# DIGTITAL.net
KiCad netlist of a schematic drawn in Altium Designer
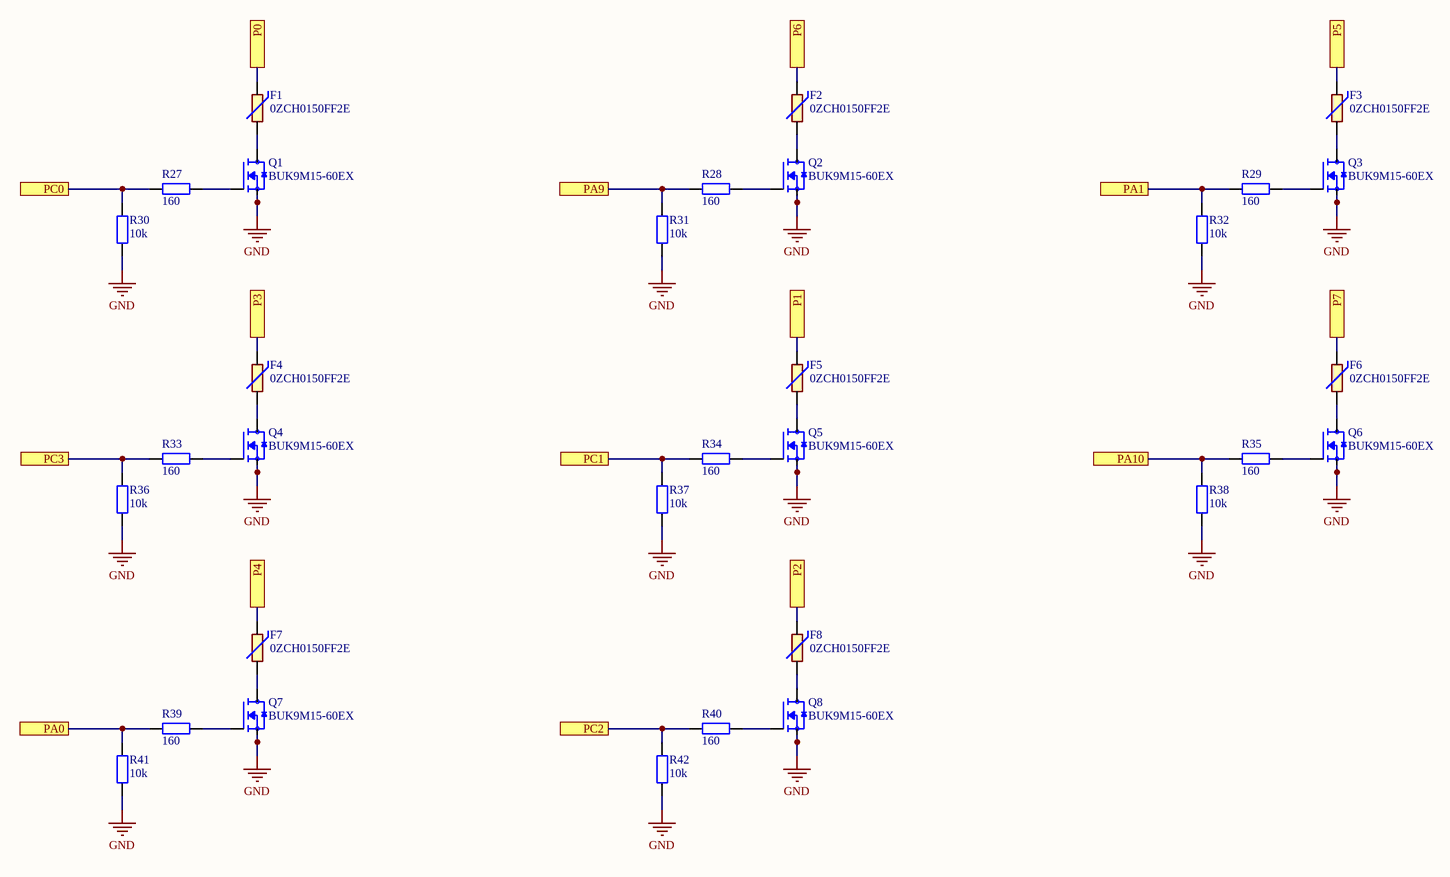
[diagram p0: DIGTITAL.SchDoc]

(export (version "E")
  (design (tool "Eeschema 10.0.6"))
  (components
    (comp (ref "F1")
      (value "0ZCH0150FF2E")
      (footprint "FUSC3225X90N")
      (description "1210 SMT PPTC ¦ 1.50 Ih ¦ 6V")
      (fields (field (name "MF") "Bel Fuse"))
      (libsource (lib "0ZCH0150FF2E") (part "0ZCH0150FF2E"))
    )
    (comp (ref "F2")
      (value "0ZCH0150FF2E")
      (footprint "FUSC3225X90N")
      (description "1210 SMT PPTC ¦ 1.50 Ih ¦ 6V")
      (fields (field (name "MF") "Bel Fuse"))
      (libsource (lib "0ZCH0150FF2E") (part "0ZCH0150FF2E"))
    )
    (comp (ref "F3")
      (value "0ZCH0150FF2E")
      (footprint "FUSC3225X90N")
      (description "1210 SMT PPTC ¦ 1.50 Ih ¦ 6V")
      (fields (field (name "MF") "Bel Fuse"))
      (libsource (lib "0ZCH0150FF2E") (part "0ZCH0150FF2E"))
    )
    (comp (ref "F4")
      (value "0ZCH0150FF2E")
      (footprint "FUSC3225X90N")
      (description "1210 SMT PPTC ¦ 1.50 Ih ¦ 6V")
      (fields (field (name "MF") "Bel Fuse"))
      (libsource (lib "0ZCH0150FF2E") (part "0ZCH0150FF2E"))
    )
    (comp (ref "F5")
      (value "0ZCH0150FF2E")
      (footprint "FUSC3225X90N")
      (description "1210 SMT PPTC ¦ 1.50 Ih ¦ 6V")
      (fields (field (name "MF") "Bel Fuse"))
      (libsource (lib "0ZCH0150FF2E") (part "0ZCH0150FF2E"))
    )
    (comp (ref "F6")
      (value "0ZCH0150FF2E")
      (footprint "FUSC3225X90N")
      (description "1210 SMT PPTC ¦ 1.50 Ih ¦ 6V")
      (fields (field (name "MF") "Bel Fuse"))
      (libsource (lib "0ZCH0150FF2E") (part "0ZCH0150FF2E"))
    )
    (comp (ref "F7")
      (value "0ZCH0150FF2E")
      (footprint "FUSC3225X90N")
      (description "1210 SMT PPTC ¦ 1.50 Ih ¦ 6V")
      (fields (field (name "MF") "Bel Fuse"))
      (libsource (lib "0ZCH0150FF2E") (part "0ZCH0150FF2E"))
    )
    (comp (ref "F8")
      (value "0ZCH0150FF2E")
      (footprint "FUSC3225X90N")
      (description "1210 SMT PPTC ¦ 1.50 Ih ¦ 6V")
      (fields (field (name "MF") "Bel Fuse"))
      (libsource (lib "0ZCH0150FF2E") (part "0ZCH0150FF2E"))
    )
    (comp (ref "Q1")
      (value "BUK9M15-60EX")
      (footprint "TRANS_BUK9M15-60EX")
      (description "Bá»™ chuyá»ƒn Ä‘á»•i N-Channel 60 V 47A (Tc) 75W (Tc) gáº¯n bá» máº·t LFPAK33")
      (fields (field (name "MF") "Nexperia USA"))
      (libsource (lib "BUK9M15-60EX") (part "BUK9M15-60EX"))
    )
    (comp (ref "Q2")
      (value "BUK9M15-60EX")
      (footprint "TRANS_BUK9M15-60EX")
      (description "Bá»™ chuyá»ƒn Ä‘á»•i N-Channel 60 V 47A (Tc) 75W (Tc) gáº¯n bá» máº·t LFPAK33")
      (fields (field (name "MF") "Nexperia USA"))
      (libsource (lib "BUK9M15-60EX") (part "BUK9M15-60EX"))
    )
    (comp (ref "Q3")
      (value "BUK9M15-60EX")
      (footprint "TRANS_BUK9M15-60EX")
      (description "Bá»™ chuyá»ƒn Ä‘á»•i N-Channel 60 V 47A (Tc) 75W (Tc) gáº¯n bá» máº·t LFPAK33")
      (fields (field (name "MF") "Nexperia USA"))
      (libsource (lib "BUK9M15-60EX") (part "BUK9M15-60EX"))
    )
    (comp (ref "Q4")
      (value "BUK9M15-60EX")
      (footprint "TRANS_BUK9M15-60EX")
      (description "Bá»™ chuyá»ƒn Ä‘á»•i N-Channel 60 V 47A (Tc) 75W (Tc) gáº¯n bá» máº·t LFPAK33")
      (fields (field (name "MF") "Nexperia USA"))
      (libsource (lib "BUK9M15-60EX") (part "BUK9M15-60EX"))
    )
    (comp (ref "Q5")
      (value "BUK9M15-60EX")
      (footprint "TRANS_BUK9M15-60EX")
      (description "Bá»™ chuyá»ƒn Ä‘á»•i N-Channel 60 V 47A (Tc) 75W (Tc) gáº¯n bá» máº·t LFPAK33")
      (fields (field (name "MF") "Nexperia USA"))
      (libsource (lib "BUK9M15-60EX") (part "BUK9M15-60EX"))
    )
    (comp (ref "Q6")
      (value "BUK9M15-60EX")
      (footprint "TRANS_BUK9M15-60EX")
      (description "Bá»™ chuyá»ƒn Ä‘á»•i N-Channel 60 V 47A (Tc) 75W (Tc) gáº¯n bá» máº·t LFPAK33")
      (fields (field (name "MF") "Nexperia USA"))
      (libsource (lib "BUK9M15-60EX") (part "BUK9M15-60EX"))
    )
    (comp (ref "Q7")
      (value "BUK9M15-60EX")
      (footprint "TRANS_BUK9M15-60EX")
      (description "Bá»™ chuyá»ƒn Ä‘á»•i N-Channel 60 V 47A (Tc) 75W (Tc) gáº¯n bá» máº·t LFPAK33")
      (fields (field (name "MF") "Nexperia USA"))
      (libsource (lib "BUK9M15-60EX") (part "BUK9M15-60EX"))
    )
    (comp (ref "Q8")
      (value "BUK9M15-60EX")
      (footprint "TRANS_BUK9M15-60EX")
      (description "Bá»™ chuyá»ƒn Ä‘á»•i N-Channel 60 V 47A (Tc) 75W (Tc) gáº¯n bá» máº·t LFPAK33")
      (fields (field (name "MF") "Nexperia USA"))
      (libsource (lib "BUK9M15-60EX") (part "BUK9M15-60EX"))
    )
    (comp (ref "R27")
      (value "160")
      (footprint "tro smd 0603")
      (description "RES")
      (libsource (lib "AUSB") (part "Tro 0603 1% 10k"))
    )
    (comp (ref "R28")
      (value "160")
      (footprint "tro smd 0603")
      (description "RES")
      (libsource (lib "AUSB") (part "Tro 0603 1% 10k"))
    )
    (comp (ref "R29")
      (value "160")
      (footprint "tro smd 0603")
      (description "RES")
      (libsource (lib "AUSB") (part "Tro 0603 1% 10k"))
    )
    (comp (ref "R30")
      (value "10k")
      (footprint "tro smd 0603")
      (description "RES")
      (libsource (lib "AUSB") (part "Tro 0603 1% 10k"))
    )
    (comp (ref "R31")
      (value "10k")
      (footprint "tro smd 0603")
      (description "RES")
      (libsource (lib "AUSB") (part "Tro 0603 1% 10k"))
    )
    (comp (ref "R32")
      (value "10k")
      (footprint "tro smd 0603")
      (description "RES")
      (libsource (lib "AUSB") (part "Tro 0603 1% 10k"))
    )
    (comp (ref "R33")
      (value "160")
      (footprint "tro smd 0603")
      (description "RES")
      (libsource (lib "AUSB") (part "Tro 0603 1% 10k"))
    )
    (comp (ref "R34")
      (value "160")
      (footprint "tro smd 0603")
      (description "RES")
      (libsource (lib "AUSB") (part "Tro 0603 1% 10k"))
    )
    (comp (ref "R35")
      (value "160")
      (footprint "tro smd 0603")
      (description "RES")
      (libsource (lib "AUSB") (part "Tro 0603 1% 10k"))
    )
    (comp (ref "R36")
      (value "10k")
      (footprint "tro smd 0603")
      (description "RES")
      (libsource (lib "AUSB") (part "Tro 0603 1% 10k"))
    )
    (comp (ref "R37")
      (value "10k")
      (footprint "tro smd 0603")
      (description "RES")
      (libsource (lib "AUSB") (part "Tro 0603 1% 10k"))
    )
    (comp (ref "R38")
      (value "10k")
      (footprint "tro smd 0603")
      (description "RES")
      (libsource (lib "AUSB") (part "Tro 0603 1% 10k"))
    )
    (comp (ref "R39")
      (value "160")
      (footprint "tro smd 0603")
      (description "RES")
      (libsource (lib "AUSB") (part "Tro 0603 1% 10k"))
    )
    (comp (ref "R40")
      (value "160")
      (footprint "tro smd 0603")
      (description "RES")
      (libsource (lib "AUSB") (part "Tro 0603 1% 10k"))
    )
    (comp (ref "R41")
      (value "10k")
      (footprint "tro smd 0603")
      (description "RES")
      (libsource (lib "AUSB") (part "Tro 0603 1% 10k"))
    )
    (comp (ref "R42")
      (value "10k")
      (footprint "tro smd 0603")
      (description "RES")
      (libsource (lib "AUSB") (part "Tro 0603 1% 10k"))
    )
  )
  (nets
    (net (code "1") (name "/P0") (class "Default")
      (node (ref "F1") (pin "1") (pinfunction "1_1") (pintype "passive"))
    )
    (net (code "2") (name "/P1") (class "Default")
      (node (ref "F5") (pin "1") (pinfunction "1_1") (pintype "passive"))
    )
    (net (code "3") (name "/P2") (class "Default")
      (node (ref "F8") (pin "1") (pinfunction "1_1") (pintype "passive"))
    )
    (net (code "4") (name "/P3") (class "Default")
      (node (ref "F4") (pin "1") (pinfunction "1_1") (pintype "passive"))
    )
    (net (code "5") (name "/P4") (class "Default")
      (node (ref "F7") (pin "1") (pinfunction "1_1") (pintype "passive"))
    )
    (net (code "6") (name "/P5") (class "Default")
      (node (ref "F3") (pin "1") (pinfunction "1_1") (pintype "passive"))
    )
    (net (code "7") (name "/P6") (class "Default")
      (node (ref "F2") (pin "1") (pinfunction "1_1") (pintype "passive"))
    )
    (net (code "8") (name "/P7") (class "Default")
      (node (ref "F6") (pin "1") (pinfunction "1_1") (pintype "passive"))
    )
    (net (code "9") (name "/PA0") (class "Default")
      (node (ref "R39") (pin "1") (pinfunction "1_1") (pintype "passive"))
      (node (ref "R41") (pin "2") (pinfunction "2_2") (pintype "passive"))
    )
    (net (code "10") (name "/PA1") (class "Default")
      (node (ref "R29") (pin "1") (pinfunction "1_1") (pintype "passive"))
      (node (ref "R32") (pin "2") (pinfunction "2_2") (pintype "passive"))
    )
    (net (code "11") (name "/PA9") (class "Default")
      (node (ref "R28") (pin "1") (pinfunction "1_1") (pintype "passive"))
      (node (ref "R31") (pin "2") (pinfunction "2_2") (pintype "passive"))
    )
    (net (code "12") (name "/PA10") (class "Default")
      (node (ref "R35") (pin "1") (pinfunction "1_1") (pintype "passive"))
      (node (ref "R38") (pin "2") (pinfunction "2_2") (pintype "passive"))
    )
    (net (code "13") (name "/PC0") (class "Default")
      (node (ref "R27") (pin "1") (pinfunction "1_1") (pintype "passive"))
      (node (ref "R30") (pin "2") (pinfunction "2_2") (pintype "passive"))
    )
    (net (code "14") (name "/PC1") (class "Default")
      (node (ref "R34") (pin "1") (pinfunction "1_1") (pintype "passive"))
      (node (ref "R37") (pin "2") (pinfunction "2_2") (pintype "passive"))
    )
    (net (code "15") (name "/PC2") (class "Default")
      (node (ref "R40") (pin "1") (pinfunction "1_1") (pintype "passive"))
      (node (ref "R42") (pin "2") (pinfunction "2_2") (pintype "passive"))
    )
    (net (code "16") (name "/PC3") (class "Default")
      (node (ref "R33") (pin "1") (pinfunction "1_1") (pintype "passive"))
      (node (ref "R36") (pin "2") (pinfunction "2_2") (pintype "passive"))
    )
    (net (code "17") (name "GND") (class "Default")
      (node (ref "Q1") (pin "1") (pinfunction "S_1") (pintype "passive"))
      (node (ref "Q1") (pin "2") (pinfunction "S_2") (pintype "passive"))
      (node (ref "Q1") (pin "3") (pinfunction "S_3") (pintype "passive"))
      (node (ref "Q2") (pin "1") (pinfunction "S_1") (pintype "passive"))
      (node (ref "Q2") (pin "2") (pinfunction "S_2") (pintype "passive"))
      (node (ref "Q2") (pin "3") (pinfunction "S_3") (pintype "passive"))
      (node (ref "Q3") (pin "1") (pinfunction "S_1") (pintype "passive"))
      (node (ref "Q3") (pin "2") (pinfunction "S_2") (pintype "passive"))
      (node (ref "Q3") (pin "3") (pinfunction "S_3") (pintype "passive"))
      (node (ref "Q4") (pin "1") (pinfunction "S_1") (pintype "passive"))
      (node (ref "Q4") (pin "2") (pinfunction "S_2") (pintype "passive"))
      (node (ref "Q4") (pin "3") (pinfunction "S_3") (pintype "passive"))
      (node (ref "Q5") (pin "1") (pinfunction "S_1") (pintype "passive"))
      (node (ref "Q5") (pin "2") (pinfunction "S_2") (pintype "passive"))
      (node (ref "Q5") (pin "3") (pinfunction "S_3") (pintype "passive"))
      (node (ref "Q6") (pin "1") (pinfunction "S_1") (pintype "passive"))
      (node (ref "Q6") (pin "2") (pinfunction "S_2") (pintype "passive"))
      (node (ref "Q6") (pin "3") (pinfunction "S_3") (pintype "passive"))
      (node (ref "Q7") (pin "1") (pinfunction "S_1") (pintype "passive"))
      (node (ref "Q7") (pin "2") (pinfunction "S_2") (pintype "passive"))
      (node (ref "Q7") (pin "3") (pinfunction "S_3") (pintype "passive"))
      (node (ref "Q8") (pin "1") (pinfunction "S_1") (pintype "passive"))
      (node (ref "Q8") (pin "2") (pinfunction "S_2") (pintype "passive"))
      (node (ref "Q8") (pin "3") (pinfunction "S_3") (pintype "passive"))
      (node (ref "R30") (pin "1") (pinfunction "1_1") (pintype "passive"))
      (node (ref "R31") (pin "1") (pinfunction "1_1") (pintype "passive"))
      (node (ref "R32") (pin "1") (pinfunction "1_1") (pintype "passive"))
      (node (ref "R36") (pin "1") (pinfunction "1_1") (pintype "passive"))
      (node (ref "R37") (pin "1") (pinfunction "1_1") (pintype "passive"))
      (node (ref "R38") (pin "1") (pinfunction "1_1") (pintype "passive"))
      (node (ref "R41") (pin "1") (pinfunction "1_1") (pintype "passive"))
      (node (ref "R42") (pin "1") (pinfunction "1_1") (pintype "passive"))
    )
    (net (code "18") (name "Net-(Q1-D)") (class "Default")
      (node (ref "F1") (pin "2") (pinfunction "2_2") (pintype "passive"))
      (node (ref "Q1") (pin "5") (pinfunction "D_5") (pintype "passive"))
    )
    (net (code "19") (name "Net-(Q1-G)") (class "Default")
      (node (ref "Q1") (pin "4") (pinfunction "G_4") (pintype "passive"))
      (node (ref "R27") (pin "2") (pinfunction "2_2") (pintype "passive"))
    )
    (net (code "20") (name "Net-(Q2-D)") (class "Default")
      (node (ref "F2") (pin "2") (pinfunction "2_2") (pintype "passive"))
      (node (ref "Q2") (pin "5") (pinfunction "D_5") (pintype "passive"))
    )
    (net (code "21") (name "Net-(Q2-G)") (class "Default")
      (node (ref "Q2") (pin "4") (pinfunction "G_4") (pintype "passive"))
      (node (ref "R28") (pin "2") (pinfunction "2_2") (pintype "passive"))
    )
    (net (code "22") (name "Net-(Q3-D)") (class "Default")
      (node (ref "F3") (pin "2") (pinfunction "2_2") (pintype "passive"))
      (node (ref "Q3") (pin "5") (pinfunction "D_5") (pintype "passive"))
    )
    (net (code "23") (name "Net-(Q3-G)") (class "Default")
      (node (ref "Q3") (pin "4") (pinfunction "G_4") (pintype "passive"))
      (node (ref "R29") (pin "2") (pinfunction "2_2") (pintype "passive"))
    )
    (net (code "24") (name "Net-(Q4-D)") (class "Default")
      (node (ref "F4") (pin "2") (pinfunction "2_2") (pintype "passive"))
      (node (ref "Q4") (pin "5") (pinfunction "D_5") (pintype "passive"))
    )
    (net (code "25") (name "Net-(Q4-G)") (class "Default")
      (node (ref "Q4") (pin "4") (pinfunction "G_4") (pintype "passive"))
      (node (ref "R33") (pin "2") (pinfunction "2_2") (pintype "passive"))
    )
    (net (code "26") (name "Net-(Q5-D)") (class "Default")
      (node (ref "F5") (pin "2") (pinfunction "2_2") (pintype "passive"))
      (node (ref "Q5") (pin "5") (pinfunction "D_5") (pintype "passive"))
    )
    (net (code "27") (name "Net-(Q5-G)") (class "Default")
      (node (ref "Q5") (pin "4") (pinfunction "G_4") (pintype "passive"))
      (node (ref "R34") (pin "2") (pinfunction "2_2") (pintype "passive"))
    )
    (net (code "28") (name "Net-(Q6-D)") (class "Default")
      (node (ref "F6") (pin "2") (pinfunction "2_2") (pintype "passive"))
      (node (ref "Q6") (pin "5") (pinfunction "D_5") (pintype "passive"))
    )
    (net (code "29") (name "Net-(Q6-G)") (class "Default")
      (node (ref "Q6") (pin "4") (pinfunction "G_4") (pintype "passive"))
      (node (ref "R35") (pin "2") (pinfunction "2_2") (pintype "passive"))
    )
    (net (code "30") (name "Net-(Q7-D)") (class "Default")
      (node (ref "F7") (pin "2") (pinfunction "2_2") (pintype "passive"))
      (node (ref "Q7") (pin "5") (pinfunction "D_5") (pintype "passive"))
    )
    (net (code "31") (name "Net-(Q7-G)") (class "Default")
      (node (ref "Q7") (pin "4") (pinfunction "G_4") (pintype "passive"))
      (node (ref "R39") (pin "2") (pinfunction "2_2") (pintype "passive"))
    )
    (net (code "32") (name "Net-(Q8-D)") (class "Default")
      (node (ref "F8") (pin "2") (pinfunction "2_2") (pintype "passive"))
      (node (ref "Q8") (pin "5") (pinfunction "D_5") (pintype "passive"))
    )
    (net (code "33") (name "Net-(Q8-G)") (class "Default")
      (node (ref "Q8") (pin "4") (pinfunction "G_4") (pintype "passive"))
      (node (ref "R40") (pin "2") (pinfunction "2_2") (pintype "passive"))
    )
  )
)
